# LTC_Soft.net
KiCad netlist of a schematic drawn in Altium Designer
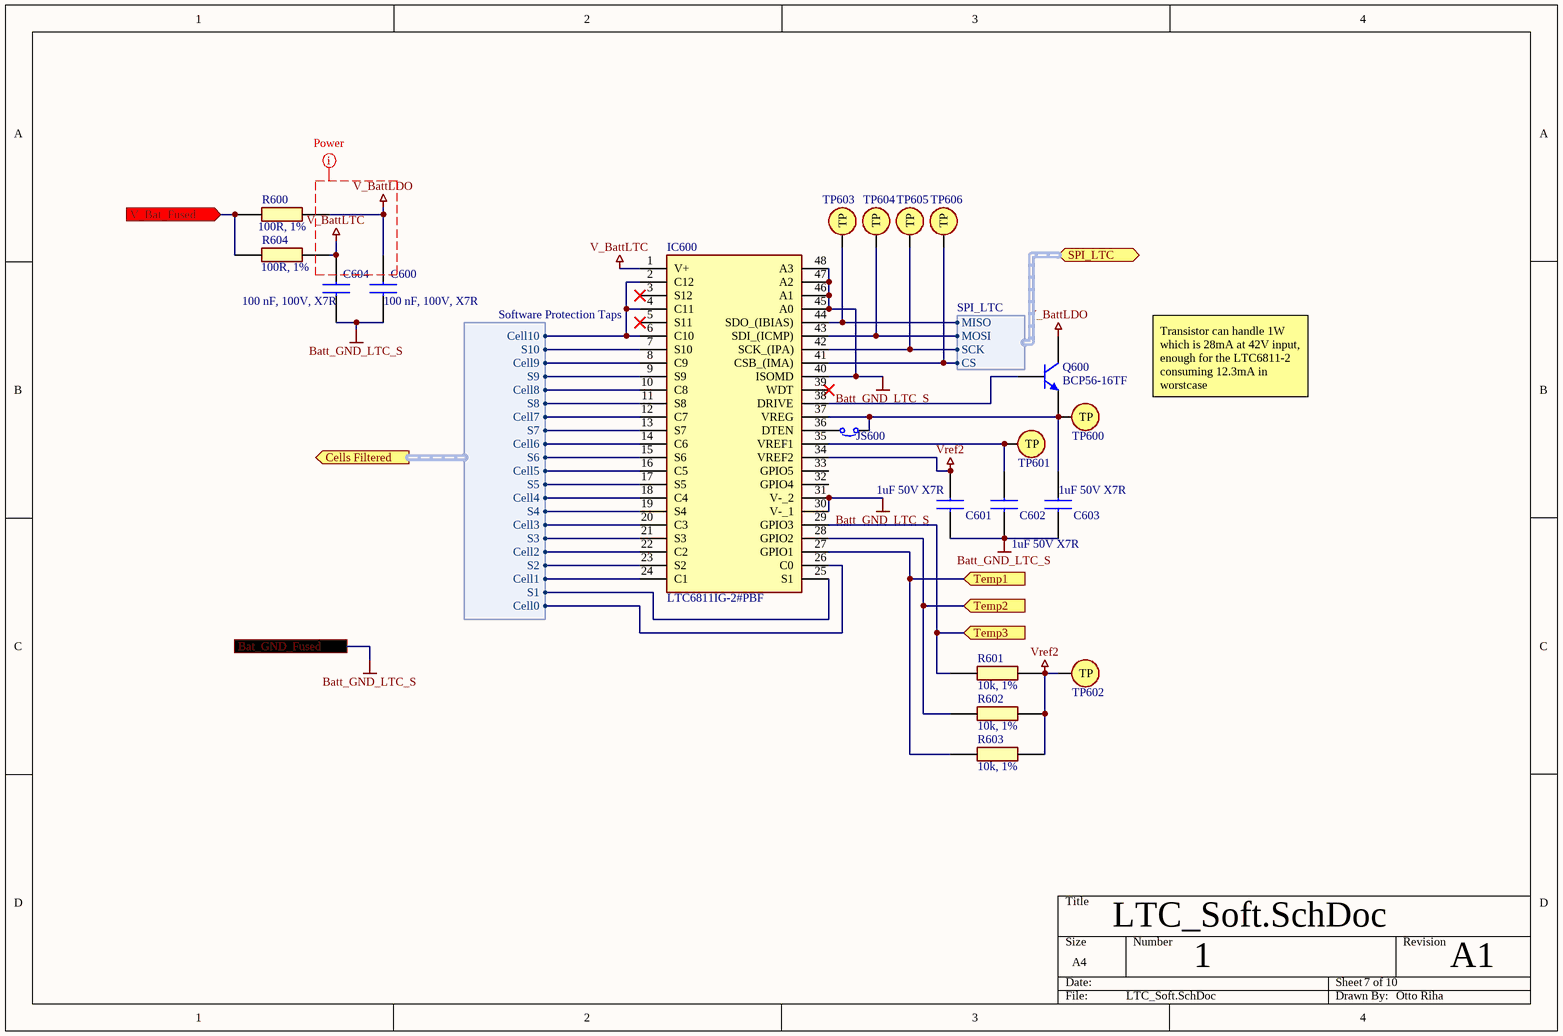
[diagram p0: LTC_Soft.SchDoc]

(export (version "E")
  (design (tool "Eeschema 10.0.6"))
  (components
    (comp (ref "C600")
      (value "100 nF, 100V, X7R")
      (footprint "SamacSys:MAJx16")
      (description "Capacitor 100nF, 100V, X7R")
      (fields
        (field (name "MANUFACTURER_PART_NUMBER") "MAJCH168BB7104KTEA01")
        (field (name "MOUSER PART NUMBER") "963-MAJCH168BB7104KT")
      )
      (libsource (lib "SamacSys") (part "MAJCH168BB7104KTEA01"))
    )
    (comp (ref "C601")
      (value "1uF 50V X7R")
      (footprint "SamacSys:CAPC1608X90N")
      (description "Capacitor 1uF 50V X7R")
      (fields
        (field (name "MANUFACTURER_PART_NUMBER") "06035C105MAT2A")
        (field (name "MOUSER PART NUMBER") "581-06035C105MAT2A")
      )
      (libsource (lib "SamacSys") (part "06035C105MAT2A"))
    )
    (comp (ref "C602")
      (value "1uF 50V X7R")
      (footprint "SamacSys:CAPC1608X90N")
      (description "Capacitor 1uF 50V X7R")
      (fields
        (field (name "MANUFACTURER_PART_NUMBER") "06035C105MAT2A")
        (field (name "MOUSER PART NUMBER") "581-06035C105MAT2A")
      )
      (libsource (lib "SamacSys") (part "06035C105MAT2A"))
    )
    (comp (ref "C603")
      (value "1uF 50V X7R")
      (footprint "SamacSys:CAPC1608X90N")
      (description "Capacitor 1uF 50V X7R")
      (fields
        (field (name "MANUFACTURER_PART_NUMBER") "06035C105MAT2A")
        (field (name "MOUSER PART NUMBER") "581-06035C105MAT2A")
      )
      (libsource (lib "SamacSys") (part "06035C105MAT2A"))
    )
    (comp (ref "C604")
      (value "100 nF, 100V, X7R")
      (footprint "SamacSys:MAJx16")
      (description "Capacitor 100nF, 100V, X7R")
      (fields
        (field (name "MANUFACTURER_PART_NUMBER") "MAJCH168BB7104KTEA01")
        (field (name "MOUSER PART NUMBER") "963-MAJCH168BB7104KT")
      )
      (libsource (lib "SamacSys") (part "MAJCH168BB7104KTEA01"))
    )
    (comp (ref "IC600")
      (value "LTC6811IG-2#PBF")
      (footprint "SamacSys:SOP50P780X200-48N")
      (description "Integrated Circuit")
      (fields (field (name "MOUSER PART NUMBER") "584-LTC6811IG-2#PBF"))
      (libsource (lib "*") (part "LTC6811IG-2#PBF"))
    )
    (comp (ref "JS600")
      (value "SolderJumper")
      (footprint "SolderJumper")
      (libsource (lib "SamacSys") (part "SolderJumper"))
    )
    (comp (ref "Q600")
      (value "BCP56-16TF")
      (footprint "SamacSys:SOT230P700X180-4N")
      (description "Transistor BJT NPN")
      (fields (field (name "MOUSER PART NUMBER") "771-BCP56-16TF"))
      (libsource (lib "SamacSys") (part "BCP56-16TF"))
    )
    (comp (ref "R600")
      (value "100R, 1%")
      (footprint "SamacSys:RESC1608X50N")
      (description "Resistor 100R, 1%")
      (fields
        (field (name "MANUFACTURER_PART_NUMBER") "CRCW0603100RFKEA")
        (field (name "MOUSER PART NUMBER") "71-CRCW0603-100-E3")
      )
      (libsource (lib "SamacSys") (part "CRCW0603100RFKEA"))
    )
    (comp (ref "R601")
      (value "10k, 1%")
      (footprint "SamacSys:RESC1608X50N")
      (description "Resistor 10k, 1%")
      (fields
        (field (name "MANUFACTURER_PART_NUMBER") "CRCW060310K0FKEI")
        (field (name "MOUSER PART NUMBER") "71-CRCW060310K0FKEI")
      )
      (libsource (lib "SamacSys") (part "CRCW060310K0FKEI"))
    )
    (comp (ref "R602")
      (value "10k, 1%")
      (footprint "SamacSys:RESC1608X50N")
      (description "Resistor 10k, 1%")
      (fields
        (field (name "MANUFACTURER_PART_NUMBER") "CRCW060310K0FKEI")
        (field (name "MOUSER PART NUMBER") "71-CRCW060310K0FKEI")
      )
      (libsource (lib "SamacSys") (part "CRCW060310K0FKEI"))
    )
    (comp (ref "R603")
      (value "10k, 1%")
      (footprint "SamacSys:RESC1608X50N")
      (description "Resistor 10k, 1%")
      (fields
        (field (name "MANUFACTURER_PART_NUMBER") "CRCW060310K0FKEI")
        (field (name "MOUSER PART NUMBER") "71-CRCW060310K0FKEI")
      )
      (libsource (lib "SamacSys") (part "CRCW060310K0FKEI"))
    )
    (comp (ref "R604")
      (value "100R, 1%")
      (footprint "SamacSys:RESC1608X50N")
      (description "Resistor 100R, 1%")
      (fields
        (field (name "MANUFACTURER_PART_NUMBER") "CRCW0603100RFKEA")
        (field (name "MOUSER PART NUMBER") "71-CRCW0603-100-E3")
      )
      (libsource (lib "SamacSys") (part "CRCW0603100RFKEA"))
    )
    (comp (ref "TP600")
      (value "Testpoint")
      (footprint "Testpoint")
      (libsource (lib "SamacSys") (part "Testpoint"))
    )
    (comp (ref "TP601")
      (value "Testpoint")
      (footprint "Testpoint")
      (libsource (lib "SamacSys") (part "Testpoint"))
    )
    (comp (ref "TP602")
      (value "Testpoint")
      (footprint "Testpoint")
      (libsource (lib "SamacSys") (part "Testpoint"))
    )
    (comp (ref "TP603")
      (value "Testpoint")
      (footprint "Testpoint")
      (libsource (lib "SamacSys") (part "Testpoint"))
    )
    (comp (ref "TP604")
      (value "Testpoint")
      (footprint "Testpoint")
      (libsource (lib "SamacSys") (part "Testpoint"))
    )
    (comp (ref "TP605")
      (value "Testpoint")
      (footprint "Testpoint")
      (libsource (lib "SamacSys") (part "Testpoint"))
    )
    (comp (ref "TP606")
      (value "Testpoint")
      (footprint "Testpoint")
      (libsource (lib "SamacSys") (part "Testpoint"))
    )
  )
  (nets
    (net (code "5") (name "/CS") (class "Default")
      (node (ref "IC600") (pin "41") (pinfunction "CSB_(IMA)_41") (pintype "passive"))
      (node (ref "TP606") (pin "1") (pinfunction "TP_1") (pintype "passive"))
    )
    (net (code "6") (name "/Cell0") (class "Default")
      (node (ref "IC600") (pin "26") (pinfunction "C0_26") (pintype "passive"))
    )
    (net (code "7") (name "/Cell1") (class "Default")
      (node (ref "IC600") (pin "24") (pinfunction "C1_24") (pintype "passive"))
    )
    (net (code "8") (name "/Cell2") (class "Default")
      (node (ref "IC600") (pin "22") (pinfunction "C2_22") (pintype "passive"))
    )
    (net (code "9") (name "/Cell3") (class "Default")
      (node (ref "IC600") (pin "20") (pinfunction "C3_20") (pintype "passive"))
    )
    (net (code "10") (name "/Cell4") (class "Default")
      (node (ref "IC600") (pin "18") (pinfunction "C4_18") (pintype "passive"))
    )
    (net (code "11") (name "/Cell5") (class "Default")
      (node (ref "IC600") (pin "16") (pinfunction "C5_16") (pintype "passive"))
    )
    (net (code "12") (name "/Cell6") (class "Default")
      (node (ref "IC600") (pin "14") (pinfunction "C6_14") (pintype "passive"))
    )
    (net (code "13") (name "/Cell7") (class "Default")
      (node (ref "IC600") (pin "12") (pinfunction "C7_12") (pintype "passive"))
    )
    (net (code "14") (name "/Cell8") (class "Default")
      (node (ref "IC600") (pin "10") (pinfunction "C8_10") (pintype "passive"))
    )
    (net (code "15") (name "/Cell9") (class "Default")
      (node (ref "IC600") (pin "8") (pinfunction "C9_8") (pintype "passive"))
    )
    (net (code "16") (name "/Cell10") (class "Default")
      (node (ref "IC600") (pin "2") (pinfunction "C12_2") (pintype "passive"))
      (node (ref "IC600") (pin "4") (pinfunction "C11_4") (pintype "passive"))
      (node (ref "IC600") (pin "6") (pinfunction "C10_6") (pintype "passive"))
    )
    (net (code "17") (name "/MISO") (class "Default")
      (node (ref "IC600") (pin "44") (pinfunction "SDO_(IBIAS)_44") (pintype "passive"))
      (node (ref "TP603") (pin "1") (pinfunction "TP_1") (pintype "passive"))
    )
    (net (code "18") (name "/MOSI") (class "Default")
      (node (ref "IC600") (pin "43") (pinfunction "SDI_(ICMP)_43") (pintype "passive"))
      (node (ref "TP604") (pin "1") (pinfunction "TP_1") (pintype "passive"))
    )
    (net (code "19") (name "/S1") (class "Default")
      (node (ref "IC600") (pin "25") (pinfunction "S1_25") (pintype "passive"))
    )
    (net (code "20") (name "/S2") (class "Default")
      (node (ref "IC600") (pin "23") (pinfunction "S2_23") (pintype "passive"))
    )
    (net (code "21") (name "/S3") (class "Default")
      (node (ref "IC600") (pin "21") (pinfunction "S3_21") (pintype "passive"))
    )
    (net (code "22") (name "/S4") (class "Default")
      (node (ref "IC600") (pin "19") (pinfunction "S4_19") (pintype "passive"))
    )
    (net (code "23") (name "/S5") (class "Default")
      (node (ref "IC600") (pin "17") (pinfunction "S5_17") (pintype "passive"))
    )
    (net (code "24") (name "/S6") (class "Default")
      (node (ref "IC600") (pin "15") (pinfunction "S6_15") (pintype "passive"))
    )
    (net (code "25") (name "/S7") (class "Default")
      (node (ref "IC600") (pin "13") (pinfunction "S7_13") (pintype "passive"))
    )
    (net (code "26") (name "/S8") (class "Default")
      (node (ref "IC600") (pin "11") (pinfunction "S8_11") (pintype "passive"))
    )
    (net (code "27") (name "/S9") (class "Default")
      (node (ref "IC600") (pin "9") (pinfunction "S9_9") (pintype "passive"))
    )
    (net (code "28") (name "/S10") (class "Default")
      (node (ref "IC600") (pin "7") (pinfunction "S10_7") (pintype "passive"))
    )
    (net (code "29") (name "/SCK") (class "Default")
      (node (ref "IC600") (pin "42") (pinfunction "SCK_(IPA)_42") (pintype "passive"))
      (node (ref "TP605") (pin "1") (pinfunction "TP_1") (pintype "passive"))
    )
    (net (code "30") (name "/Temp1") (class "Default")
      (node (ref "IC600") (pin "27") (pinfunction "GPIO1_27") (pintype "passive"))
      (node (ref "R603") (pin "2") (pinfunction "2_2") (pintype "passive"))
    )
    (net (code "31") (name "/Temp2") (class "Default")
      (node (ref "IC600") (pin "28") (pinfunction "GPIO2_28") (pintype "passive"))
      (node (ref "R602") (pin "2") (pinfunction "2_2") (pintype "passive"))
    )
    (net (code "32") (name "/Temp3") (class "Default")
      (node (ref "IC600") (pin "29") (pinfunction "GPIO3_29") (pintype "passive"))
      (node (ref "R601") (pin "2") (pinfunction "2_2") (pintype "passive"))
    )
    (net (code "33") (name "/V_Bat_Fused") (class "Default")
      (node (ref "R600") (pin "1") (pinfunction "1_1") (pintype "passive"))
      (node (ref "R604") (pin "1") (pinfunction "1_1") (pintype "passive"))
    )
    (net (code "36") (name "Batt_GND_LTC_S") (class "Default")
      (node (ref "C600") (pin "1") (pinfunction "1_1") (pintype "passive"))
      (node (ref "C601") (pin "2") (pinfunction "2_2") (pintype "passive"))
      (node (ref "C602") (pin "2") (pinfunction "2_2") (pintype "passive"))
      (node (ref "C603") (pin "2") (pinfunction "2_2") (pintype "passive"))
      (node (ref "C604") (pin "1") (pinfunction "1_1") (pintype "passive"))
      (node (ref "IC600") (pin "30") (pinfunction "V-_1_30") (pintype "passive"))
      (node (ref "IC600") (pin "31") (pinfunction "V-_2_31") (pintype "passive"))
      (node (ref "IC600") (pin "40") (pinfunction "ISOMD_40") (pintype "passive"))
      (node (ref "IC600") (pin "45") (pinfunction "A0_45") (pintype "passive"))
      (node (ref "IC600") (pin "46") (pinfunction "A1_46") (pintype "passive"))
      (node (ref "IC600") (pin "47") (pinfunction "A2_47") (pintype "passive"))
      (node (ref "IC600") (pin "48") (pinfunction "A3_48") (pintype "passive"))
    )
    (net (code "37") (name "Net-(IC600-DRIVE)") (class "Default")
      (node (ref "IC600") (pin "38") (pinfunction "DRIVE_38") (pintype "passive"))
      (node (ref "Q600") (pin "1") (pinfunction "B_1") (pintype "passive"))
    )
    (net (code "38") (name "Net-(IC600-DTEN)") (class "Default")
      (node (ref "IC600") (pin "36") (pinfunction "DTEN_36") (pintype "passive"))
      (node (ref "JS600") (pin "1") (pinfunction "1_1") (pintype "passive"))
    )
    (net (code "39") (name "Net-(IC600-VREF1)") (class "Default")
      (node (ref "C602") (pin "1") (pinfunction "1_1") (pintype "passive"))
      (node (ref "IC600") (pin "35") (pinfunction "VREF1_35") (pintype "passive"))
      (node (ref "TP601") (pin "1") (pinfunction "TP_1") (pintype "passive"))
    )
    (net (code "40") (name "Net-(IC600-VREG)") (class "Default")
      (node (ref "C603") (pin "1") (pinfunction "1_1") (pintype "passive"))
      (node (ref "IC600") (pin "37") (pinfunction "VREG_37") (pintype "passive"))
      (node (ref "JS600") (pin "2") (pinfunction "2_2") (pintype "passive"))
      (node (ref "Q600") (pin "3") (pinfunction "E_3") (pintype "passive"))
      (node (ref "TP600") (pin "1") (pinfunction "TP_1") (pintype "passive"))
    )
    (net (code "41") (name "V_BattLDO") (class "Default")
      (node (ref "C600") (pin "2") (pinfunction "2_2") (pintype "passive"))
      (node (ref "Q600") (pin "2") (pinfunction "C_2") (pintype "power_in"))
      (node (ref "R600") (pin "2") (pinfunction "2_2") (pintype "passive"))
    )
    (net (code "42") (name "V_BattLTC") (class "Default")
      (node (ref "C604") (pin "2") (pinfunction "2_2") (pintype "passive"))
      (node (ref "IC600") (pin "1") (pinfunction "V+_1") (pintype "passive"))
      (node (ref "R604") (pin "2") (pinfunction "2_2") (pintype "passive"))
    )
    (net (code "43") (name "Vref2") (class "Default")
      (node (ref "C601") (pin "1") (pinfunction "1_1") (pintype "passive"))
      (node (ref "IC600") (pin "34") (pinfunction "VREF2_34") (pintype "passive"))
      (node (ref "R601") (pin "1") (pinfunction "1_1") (pintype "passive"))
      (node (ref "R602") (pin "1") (pinfunction "1_1") (pintype "passive"))
      (node (ref "R603") (pin "1") (pinfunction "1_1") (pintype "passive"))
      (node (ref "TP602") (pin "1") (pinfunction "TP_1") (pintype "passive"))
    )
    (net (code "44") (name "unconnected-(IC600-GPIO4-Pad32)") (class "Default")
      (node (ref "IC600") (pin "32") (pinfunction "GPIO4_32") (pintype "passive"))
    )
    (net (code "45") (name "unconnected-(IC600-GPIO5-Pad33)") (class "Default")
      (node (ref "IC600") (pin "33") (pinfunction "GPIO5_33") (pintype "passive"))
    )
    (net (code "46") (name "unconnected-(IC600-S11-Pad5)") (class "Default")
      (node (ref "IC600") (pin "5") (pinfunction "S11_5") (pintype "passive+no_connect"))
    )
    (net (code "47") (name "unconnected-(IC600-S12-Pad3)") (class "Default")
      (node (ref "IC600") (pin "3") (pinfunction "S12_3") (pintype "passive+no_connect"))
    )
    (net (code "48") (name "unconnected-(IC600-WDT-Pad39)") (class "Default")
      (node (ref "IC600") (pin "39") (pinfunction "WDT_39") (pintype "passive+no_connect"))
    )
  )
)
